# us8.net
KiCad netlist of a schematic drawn in EAGLE
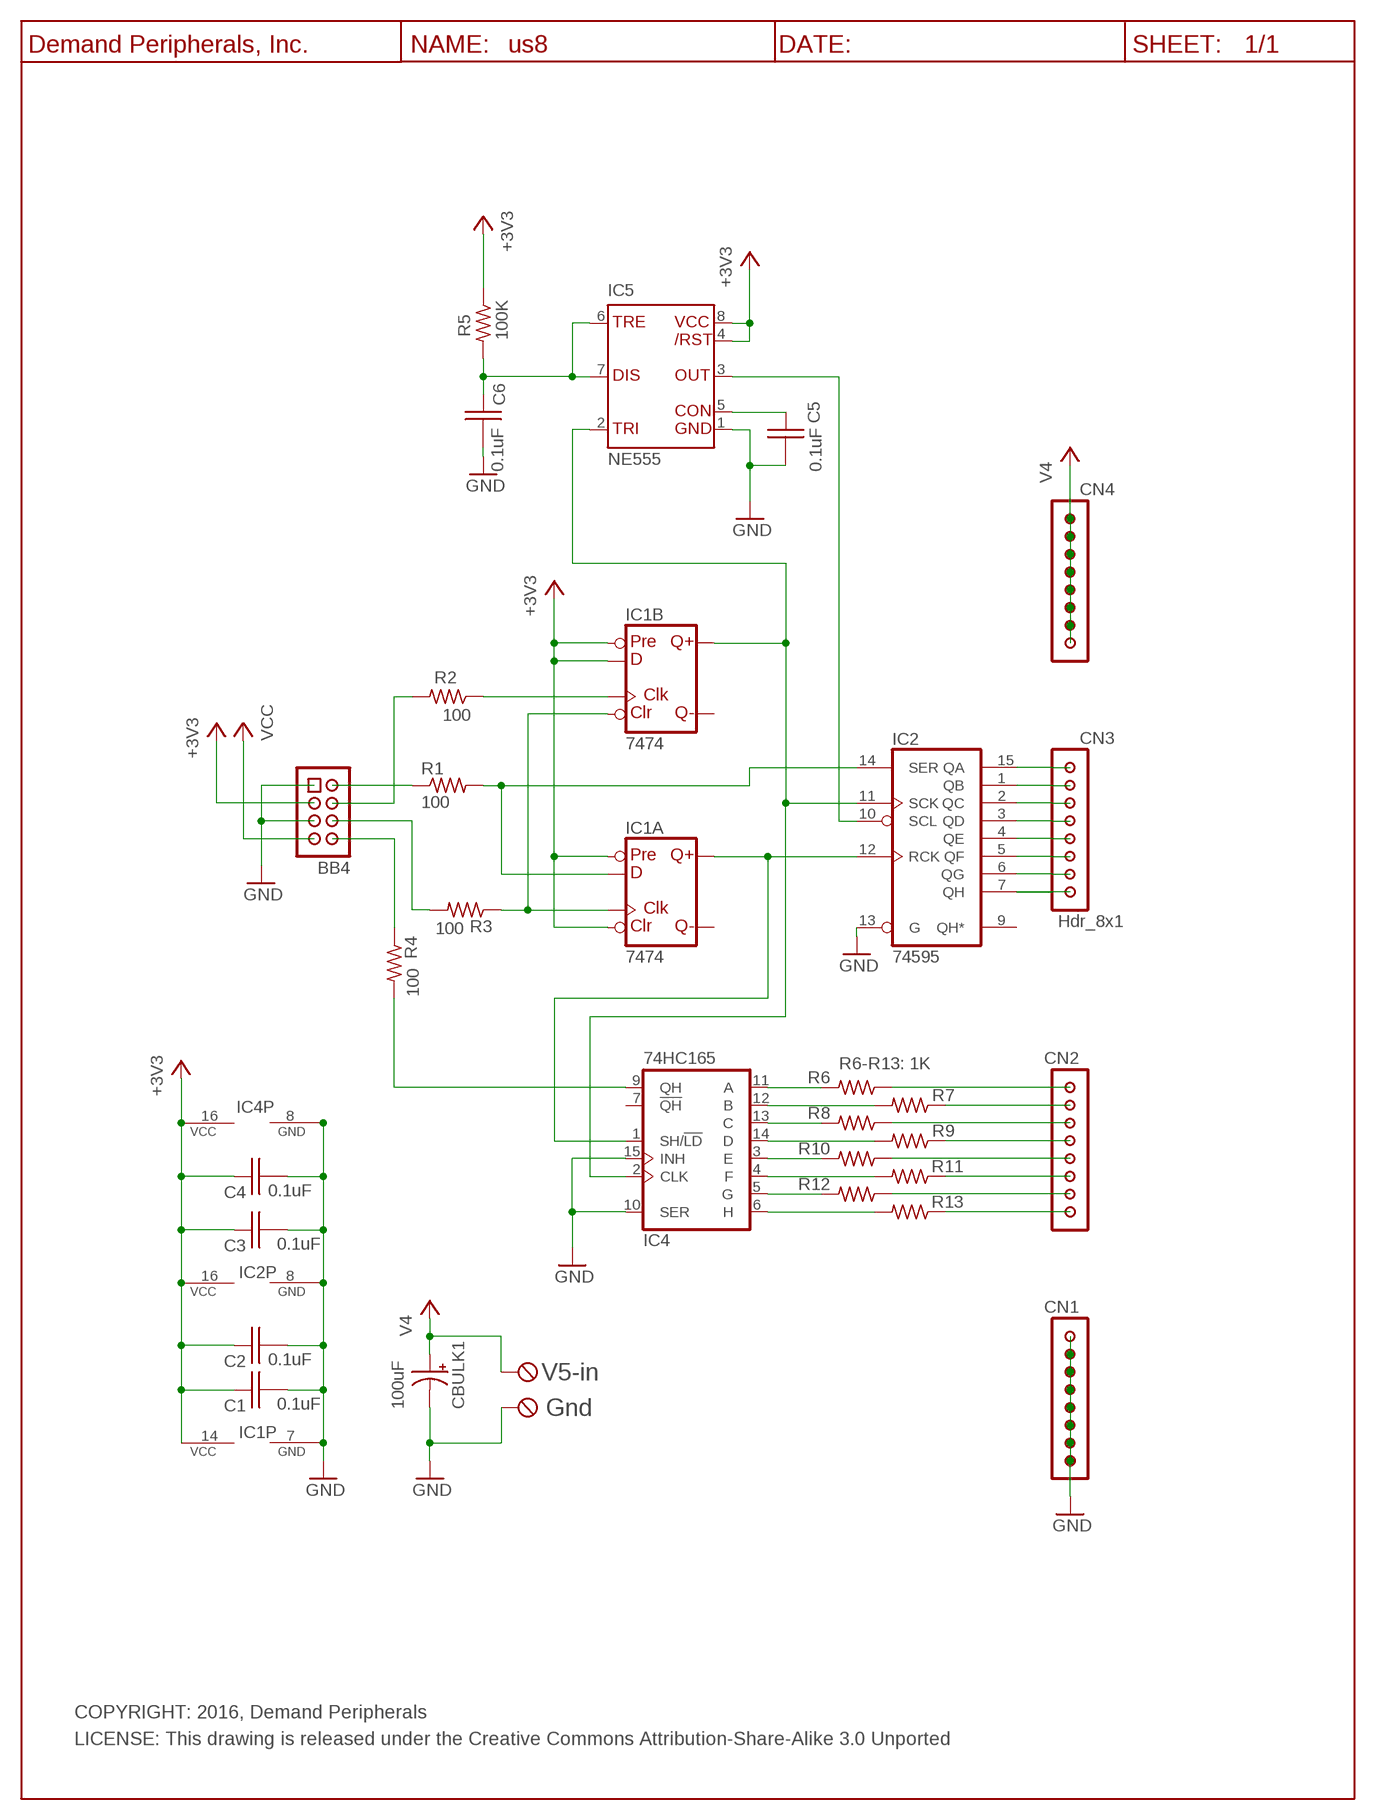
[diagram p0: schematic, sheet 1]

(export (version "E")
  (design (tool "Eeschema 10.0.6"))
  (components
    (comp (ref "BB4")
      (value "Hdr_4x2")
      (footprint "eagle-import:HDR-4X2")
      (libsource (lib "eagle-import") (part "HDR-4X2-SHR"))
    )
    (comp (ref "C1")
      (value "0.1uF")
      (footprint "eagle-import:C0603")
      (libsource (lib "eagle-import") (part "C0.1UF_C0603"))
    )
    (comp (ref "C2")
      (value "0.1uF")
      (footprint "eagle-import:C0603")
      (libsource (lib "eagle-import") (part "C0.1UF_C0603"))
    )
    (comp (ref "C3")
      (value "0.1uF")
      (footprint "eagle-import:C0603")
      (libsource (lib "eagle-import") (part "C0.1UF_C0603"))
    )
    (comp (ref "C4")
      (value "0.1uF")
      (footprint "eagle-import:C0603")
      (libsource (lib "eagle-import") (part "C0.1UF_C0603"))
    )
    (comp (ref "C5")
      (value "0.1uF")
      (footprint "eagle-import:C0603")
      (libsource (lib "eagle-import") (part "C0.1UF_C0603"))
    )
    (comp (ref "C6")
      (value "0.1uF")
      (footprint "eagle-import:C0603")
      (libsource (lib "eagle-import") (part "C0.1UF_C0603"))
    )
    (comp (ref "CBULK1")
      (value "100uF")
      (footprint "eagle-import:E3.5-8")
      (libsource (lib "eagle-import") (part "C100UF_E3.5-8"))
    )
    (comp (ref "CN1")
      (value "Hdr_8x1")
      (footprint "eagle-import:HDR-8X1-NOP1")
      (libsource (lib "eagle-import") (part "HDR-8X1-NOP1"))
    )
    (comp (ref "CN2")
      (value "Hdr_8x1")
      (footprint "eagle-import:HDR-8X1-NOP1")
      (libsource (lib "eagle-import") (part "HDR-8X1-NOP1"))
    )
    (comp (ref "CN3")
      (value "Hdr_8x1")
      (footprint "eagle-import:HDR-8X1-NOP1")
      (libsource (lib "eagle-import") (part "HDR-8X1-NOP1"))
    )
    (comp (ref "CN4")
      (value "Hdr_8x1")
      (footprint "eagle-import:HDR-8X1-NOP1")
      (libsource (lib "eagle-import") (part "HDR-8X1-NOP1"))
    )
    (comp (ref "CN5")
      (value "TBLK-5.08-X2")
      (footprint "eagle-import:TBLK-5.08-X2")
      (libsource (lib "eagle-import") (part "TBLK-5.08-X2"))
    )
    (comp (ref "IC1")
      (value "7474")
      (footprint "eagle-import:SO14")
      (libsource (lib "eagle-import") (part "74AHC74SS"))
    )
    (comp (ref "IC2")
      (value "74595")
      (footprint "eagle-import:SO16")
      (libsource (lib "eagle-import") (part "74595"))
    )
    (comp (ref "IC4")
      (value "74HC165")
      (footprint "eagle-import:SO16")
      (libsource (lib "eagle-import") (part "74HC165"))
    )
    (comp (ref "IC5")
      (value "NE555")
      (footprint "eagle-import:SOIC8")
      (libsource (lib "eagle-import") (part "NE555"))
    )
    (comp (ref "R1")
      (value "100")
      (footprint "eagle-import:R0603")
      (libsource (lib "eagle-import") (part "R100_R0603"))
    )
    (comp (ref "R2")
      (value "100")
      (footprint "eagle-import:R0603")
      (libsource (lib "eagle-import") (part "R100_R0603"))
    )
    (comp (ref "R3")
      (value "100")
      (footprint "eagle-import:R0603")
      (libsource (lib "eagle-import") (part "R100_R0603"))
    )
    (comp (ref "R4")
      (value "100")
      (footprint "eagle-import:R0603")
      (libsource (lib "eagle-import") (part "R100_R0603"))
    )
    (comp (ref "R5")
      (value "100K")
      (footprint "eagle-import:R0603")
      (libsource (lib "eagle-import") (part "R100K_R0603"))
    )
    (comp (ref "R6")
      (value "1K")
      (footprint "eagle-import:R0603")
      (libsource (lib "eagle-import") (part "R1K_R0603"))
    )
    (comp (ref "R7")
      (value "1K")
      (footprint "eagle-import:R0603")
      (libsource (lib "eagle-import") (part "R1K_R0603"))
    )
    (comp (ref "R8")
      (value "1K")
      (footprint "eagle-import:R0603")
      (libsource (lib "eagle-import") (part "R1K_R0603"))
    )
    (comp (ref "R9")
      (value "1K")
      (footprint "eagle-import:R0603")
      (libsource (lib "eagle-import") (part "R1K_R0603"))
    )
    (comp (ref "R10")
      (value "1K")
      (footprint "eagle-import:R0603")
      (libsource (lib "eagle-import") (part "R1K_R0603"))
    )
    (comp (ref "R11")
      (value "1K")
      (footprint "eagle-import:R0603")
      (libsource (lib "eagle-import") (part "R1K_R0603"))
    )
    (comp (ref "R12")
      (value "1K")
      (footprint "eagle-import:R0603")
      (libsource (lib "eagle-import") (part "R1K_R0603"))
    )
    (comp (ref "R13")
      (value "1K")
      (footprint "eagle-import:R0603")
      (libsource (lib "eagle-import") (part "R1K_R0603"))
    )
    (comp (ref "U$4")
      (value "DP_FRAME_P")
      (footprint "eagle-import:P_FRAME")
      (libsource (lib "eagle-import") (part "DP_FRAME_P"))
    )
  )
  (nets
    (net (code "1") (name "+3V3") (class "Default")
      (node (ref "BB4") (pin "3") (pinfunction "3_3") (pintype "passive"))
      (node (ref "C1") (pin "1") (pinfunction "1_1") (pintype "passive"))
      (node (ref "C2") (pin "1") (pinfunction "1_1") (pintype "passive"))
      (node (ref "C3") (pin "1") (pinfunction "1_1") (pintype "passive"))
      (node (ref "C4") (pin "1") (pinfunction "1_1") (pintype "passive"))
      (node (ref "IC1") (pin "1") (pinfunction "CLR_1") (pintype "input"))
      (node (ref "IC1") (pin "10") (pinfunction "PRE_10") (pintype "input"))
      (node (ref "IC1") (pin "12") (pinfunction "D_12") (pintype "input"))
      (node (ref "IC1") (pin "14") (pinfunction "VCC_14") (pintype "power_in"))
      (node (ref "IC1") (pin "4") (pinfunction "PRE_4") (pintype "input"))
      (node (ref "IC2") (pin "16") (pinfunction "VCC_16") (pintype "power_in"))
      (node (ref "IC4") (pin "16") (pinfunction "VCC_16") (pintype "power_in"))
      (node (ref "IC5") (pin "4") (pinfunction "/RES_4") (pintype "input"))
      (node (ref "IC5") (pin "8") (pinfunction "VCC+_8") (pintype "power_in"))
      (node (ref "R5") (pin "1") (pinfunction "1_1") (pintype "passive"))
    )
    (net (code "2") (name "GND") (class "Default")
      (node (ref "BB4") (pin "1") (pinfunction "1_1") (pintype "passive"))
      (node (ref "BB4") (pin "5") (pinfunction "5_5") (pintype "passive"))
      (node (ref "C1") (pin "2") (pinfunction "2_2") (pintype "passive"))
      (node (ref "C2") (pin "2") (pinfunction "2_2") (pintype "passive"))
      (node (ref "C3") (pin "2") (pinfunction "2_2") (pintype "passive"))
      (node (ref "C4") (pin "2") (pinfunction "2_2") (pintype "passive"))
      (node (ref "C5") (pin "2") (pinfunction "2_2") (pintype "passive"))
      (node (ref "C6") (pin "2") (pinfunction "2_2") (pintype "passive"))
      (node (ref "CBULK1") (pin "-") (pinfunction "-_-") (pintype "passive"))
      (node (ref "CN1") (pin "1") (pinfunction "1_1") (pintype "passive"))
      (node (ref "CN1") (pin "2") (pinfunction "2_2") (pintype "passive"))
      (node (ref "CN1") (pin "3") (pinfunction "3_3") (pintype "passive"))
      (node (ref "CN1") (pin "4") (pinfunction "4_4") (pintype "passive"))
      (node (ref "CN1") (pin "5") (pinfunction "5_5") (pintype "passive"))
      (node (ref "CN1") (pin "6") (pinfunction "6_6") (pintype "passive"))
      (node (ref "CN1") (pin "7") (pinfunction "7_7") (pintype "passive"))
      (node (ref "CN1") (pin "8") (pinfunction "8_8") (pintype "passive"))
      (node (ref "CN5") (pin "1") (pinfunction "KL_1") (pintype "passive"))
      (node (ref "IC1") (pin "7") (pinfunction "GND_7") (pintype "power_in"))
      (node (ref "IC2") (pin "13") (pinfunction "G_13") (pintype "input"))
      (node (ref "IC2") (pin "8") (pinfunction "GND_8") (pintype "power_in"))
      (node (ref "IC4") (pin "10") (pinfunction "SER_10") (pintype "input"))
      (node (ref "IC4") (pin "15") (pinfunction "INH_15") (pintype "input"))
      (node (ref "IC4") (pin "8") (pinfunction "GND_8") (pintype "power_in"))
      (node (ref "IC5") (pin "1") (pinfunction "GND_1") (pintype "power_in"))
    )
    (net (code "3") (name "Net-(BB4-Pad2)") (class "Default")
      (node (ref "BB4") (pin "2") (pinfunction "2_2") (pintype "passive"))
      (node (ref "R1") (pin "1") (pinfunction "1_1") (pintype "passive"))
    )
    (net (code "4") (name "Net-(BB4-Pad4)") (class "Default")
      (node (ref "BB4") (pin "4") (pinfunction "4_4") (pintype "passive"))
      (node (ref "R2") (pin "2") (pinfunction "2_2") (pintype "passive"))
    )
    (net (code "5") (name "Net-(BB4-Pad6)") (class "Default")
      (node (ref "BB4") (pin "6") (pinfunction "6_6") (pintype "passive"))
      (node (ref "R3") (pin "2") (pinfunction "2_2") (pintype "passive"))
    )
    (net (code "6") (name "Net-(BB4-Pad8)") (class "Default")
      (node (ref "BB4") (pin "8") (pinfunction "8_8") (pintype "passive"))
      (node (ref "R4") (pin "1") (pinfunction "1_1") (pintype "passive"))
    )
    (net (code "7") (name "Net-(CN2-Pad1)") (class "Default")
      (node (ref "CN2") (pin "1") (pinfunction "1_1") (pintype "passive"))
      (node (ref "R13") (pin "1") (pinfunction "1_1") (pintype "passive"))
    )
    (net (code "8") (name "Net-(CN2-Pad2)") (class "Default")
      (node (ref "CN2") (pin "2") (pinfunction "2_2") (pintype "passive"))
      (node (ref "R12") (pin "1") (pinfunction "1_1") (pintype "passive"))
    )
    (net (code "9") (name "Net-(CN2-Pad3)") (class "Default")
      (node (ref "CN2") (pin "3") (pinfunction "3_3") (pintype "passive"))
      (node (ref "R11") (pin "1") (pinfunction "1_1") (pintype "passive"))
    )
    (net (code "10") (name "Net-(CN2-Pad4)") (class "Default")
      (node (ref "CN2") (pin "4") (pinfunction "4_4") (pintype "passive"))
      (node (ref "R10") (pin "1") (pinfunction "1_1") (pintype "passive"))
    )
    (net (code "11") (name "Net-(CN2-Pad5)") (class "Default")
      (node (ref "CN2") (pin "5") (pinfunction "5_5") (pintype "passive"))
      (node (ref "R9") (pin "1") (pinfunction "1_1") (pintype "passive"))
    )
    (net (code "12") (name "Net-(CN2-Pad6)") (class "Default")
      (node (ref "CN2") (pin "6") (pinfunction "6_6") (pintype "passive"))
      (node (ref "R8") (pin "1") (pinfunction "1_1") (pintype "passive"))
    )
    (net (code "13") (name "Net-(CN2-Pad7)") (class "Default")
      (node (ref "CN2") (pin "7") (pinfunction "7_7") (pintype "passive"))
      (node (ref "R7") (pin "1") (pinfunction "1_1") (pintype "passive"))
    )
    (net (code "14") (name "Net-(CN2-Pad8)") (class "Default")
      (node (ref "CN2") (pin "8") (pinfunction "8_8") (pintype "passive"))
      (node (ref "R6") (pin "1") (pinfunction "1_1") (pintype "passive"))
    )
    (net (code "15") (name "Net-(IC1A-CLK)") (class "Default")
      (node (ref "IC1") (pin "13") (pinfunction "CLR_13") (pintype "input"))
      (node (ref "IC1") (pin "3") (pinfunction "CLK_3") (pintype "input"))
      (node (ref "R3") (pin "1") (pinfunction "1_1") (pintype "passive"))
    )
    (net (code "16") (name "Net-(IC1A-D)") (class "Default")
      (node (ref "IC1") (pin "2") (pinfunction "D_2") (pintype "input"))
      (node (ref "IC2") (pin "14") (pinfunction "SER_14") (pintype "input"))
      (node (ref "R1") (pin "2") (pinfunction "2_2") (pintype "passive"))
    )
    (net (code "17") (name "Net-(IC1A-Q)") (class "Default")
      (node (ref "IC1") (pin "5") (pinfunction "Q_5") (pintype "output"))
      (node (ref "IC2") (pin "12") (pinfunction "RCK_12") (pintype "input"))
      (node (ref "IC4") (pin "1") (pinfunction "SH/~{LD}_1") (pintype "input"))
    )
    (net (code "18") (name "Net-(IC1B-CLK)") (class "Default")
      (node (ref "IC1") (pin "11") (pinfunction "CLK_11") (pintype "input"))
      (node (ref "R2") (pin "1") (pinfunction "1_1") (pintype "passive"))
    )
    (net (code "19") (name "Net-(IC1B-Q)") (class "Default")
      (node (ref "IC1") (pin "9") (pinfunction "Q_9") (pintype "output"))
      (node (ref "IC2") (pin "11") (pinfunction "SCK_11") (pintype "input"))
      (node (ref "IC4") (pin "2") (pinfunction "CLK_2") (pintype "input"))
      (node (ref "IC5") (pin "2") (pinfunction "TRI_2") (pintype "input"))
    )
    (net (code "20") (name "Net-(IC2A-QA)") (class "Default")
      (node (ref "CN3") (pin "8") (pinfunction "8_8") (pintype "passive"))
      (node (ref "IC2") (pin "15") (pinfunction "QA_15") (pintype "tri_state"))
    )
    (net (code "21") (name "Net-(IC2A-QB)") (class "Default")
      (node (ref "CN3") (pin "7") (pinfunction "7_7") (pintype "passive"))
      (node (ref "IC2") (pin "1") (pinfunction "QB_1") (pintype "tri_state"))
    )
    (net (code "22") (name "Net-(IC2A-QC)") (class "Default")
      (node (ref "CN3") (pin "6") (pinfunction "6_6") (pintype "passive"))
      (node (ref "IC2") (pin "2") (pinfunction "QC_2") (pintype "tri_state"))
    )
    (net (code "23") (name "Net-(IC2A-QD)") (class "Default")
      (node (ref "CN3") (pin "5") (pinfunction "5_5") (pintype "passive"))
      (node (ref "IC2") (pin "3") (pinfunction "QD_3") (pintype "tri_state"))
    )
    (net (code "24") (name "Net-(IC2A-QE)") (class "Default")
      (node (ref "CN3") (pin "4") (pinfunction "4_4") (pintype "passive"))
      (node (ref "IC2") (pin "4") (pinfunction "QE_4") (pintype "tri_state"))
    )
    (net (code "25") (name "Net-(IC2A-QF)") (class "Default")
      (node (ref "CN3") (pin "3") (pinfunction "3_3") (pintype "passive"))
      (node (ref "IC2") (pin "5") (pinfunction "QF_5") (pintype "tri_state"))
    )
    (net (code "26") (name "Net-(IC2A-QG)") (class "Default")
      (node (ref "CN3") (pin "2") (pinfunction "2_2") (pintype "passive"))
      (node (ref "IC2") (pin "6") (pinfunction "QG_6") (pintype "tri_state"))
    )
    (net (code "27") (name "Net-(IC2A-QH)") (class "Default")
      (node (ref "CN3") (pin "1") (pinfunction "1_1") (pintype "passive"))
      (node (ref "IC2") (pin "7") (pinfunction "QH_7") (pintype "tri_state"))
    )
    (net (code "28") (name "Net-(IC2A-SCL)") (class "Default")
      (node (ref "IC2") (pin "10") (pinfunction "SCL_10") (pintype "input"))
      (node (ref "IC5") (pin "3") (pinfunction "OUT_3") (pintype "output"))
    )
    (net (code "29") (name "Net-(IC4A-A)") (class "Default")
      (node (ref "IC4") (pin "11") (pinfunction "A_11") (pintype "input"))
      (node (ref "R6") (pin "2") (pinfunction "2_2") (pintype "passive"))
    )
    (net (code "30") (name "Net-(IC4A-B)") (class "Default")
      (node (ref "IC4") (pin "12") (pinfunction "B_12") (pintype "input"))
      (node (ref "R7") (pin "2") (pinfunction "2_2") (pintype "passive"))
    )
    (net (code "31") (name "Net-(IC4A-C)") (class "Default")
      (node (ref "IC4") (pin "13") (pinfunction "C_13") (pintype "input"))
      (node (ref "R8") (pin "2") (pinfunction "2_2") (pintype "passive"))
    )
    (net (code "32") (name "Net-(IC4A-D)") (class "Default")
      (node (ref "IC4") (pin "14") (pinfunction "D_14") (pintype "input"))
      (node (ref "R9") (pin "2") (pinfunction "2_2") (pintype "passive"))
    )
    (net (code "33") (name "Net-(IC4A-E)") (class "Default")
      (node (ref "IC4") (pin "3") (pinfunction "E_3") (pintype "input"))
      (node (ref "R10") (pin "2") (pinfunction "2_2") (pintype "passive"))
    )
    (net (code "34") (name "Net-(IC4A-F)") (class "Default")
      (node (ref "IC4") (pin "4") (pinfunction "F_4") (pintype "input"))
      (node (ref "R11") (pin "2") (pinfunction "2_2") (pintype "passive"))
    )
    (net (code "35") (name "Net-(IC4A-G)") (class "Default")
      (node (ref "IC4") (pin "5") (pinfunction "G_5") (pintype "input"))
      (node (ref "R12") (pin "2") (pinfunction "2_2") (pintype "passive"))
    )
    (net (code "36") (name "Net-(IC4A-H)") (class "Default")
      (node (ref "IC4") (pin "6") (pinfunction "H_6") (pintype "input"))
      (node (ref "R13") (pin "2") (pinfunction "2_2") (pintype "passive"))
    )
    (net (code "37") (name "Net-(IC4A-QH)") (class "Default")
      (node (ref "IC4") (pin "9") (pinfunction "QH_9") (pintype "output"))
      (node (ref "R4") (pin "2") (pinfunction "2_2") (pintype "passive"))
    )
    (net (code "38") (name "Net-(IC5-CON)") (class "Default")
      (node (ref "C5") (pin "1") (pinfunction "1_1") (pintype "passive"))
      (node (ref "IC5") (pin "5") (pinfunction "CON_5") (pintype "input"))
    )
    (net (code "39") (name "Net-(IC5-DIS)") (class "Default")
      (node (ref "C6") (pin "1") (pinfunction "1_1") (pintype "passive"))
      (node (ref "IC5") (pin "6") (pinfunction "TRE_6") (pintype "input"))
      (node (ref "IC5") (pin "7") (pinfunction "DIS_7") (pintype "input"))
      (node (ref "R5") (pin "2") (pinfunction "2_2") (pintype "passive"))
    )
    (net (code "40") (name "V4") (class "Default")
      (node (ref "CBULK1") (pin "+") (pinfunction "+_+") (pintype "passive"))
      (node (ref "CN4") (pin "1") (pinfunction "1_1") (pintype "passive"))
      (node (ref "CN4") (pin "2") (pinfunction "2_2") (pintype "passive"))
      (node (ref "CN4") (pin "3") (pinfunction "3_3") (pintype "passive"))
      (node (ref "CN4") (pin "4") (pinfunction "4_4") (pintype "passive"))
      (node (ref "CN4") (pin "5") (pinfunction "5_5") (pintype "passive"))
      (node (ref "CN4") (pin "6") (pinfunction "6_6") (pintype "passive"))
      (node (ref "CN4") (pin "7") (pinfunction "7_7") (pintype "passive"))
      (node (ref "CN4") (pin "8") (pinfunction "8_8") (pintype "passive"))
      (node (ref "CN5") (pin "2") (pinfunction "KL1_2") (pintype "passive"))
    )
    (net (code "41") (name "VCC") (class "Default")
      (node (ref "BB4") (pin "7") (pinfunction "7_7") (pintype "passive"))
    )
    (net (code "42") (name "unconnected-(IC1A-~{Q}-Pad6)") (class "Default")
      (node (ref "IC1") (pin "6") (pinfunction "~{Q}_6") (pintype "output"))
    )
    (net (code "43") (name "unconnected-(IC1B-~{Q}-Pad8)") (class "Default")
      (node (ref "IC1") (pin "8") (pinfunction "~{Q}_8") (pintype "output"))
    )
    (net (code "44") (name "unconnected-(IC2A-QH*-Pad9)") (class "Default")
      (node (ref "IC2") (pin "9") (pinfunction "QH*_9") (pintype "tri_state"))
    )
    (net (code "45") (name "unconnected-(IC4A-~{QH}-Pad7)") (class "Default")
      (node (ref "IC4") (pin "7") (pinfunction "~{QH}_7") (pintype "output"))
    )
  )
)
